# MCU_3_6.net
KiCad netlist of a schematic drawn in Altium Designer
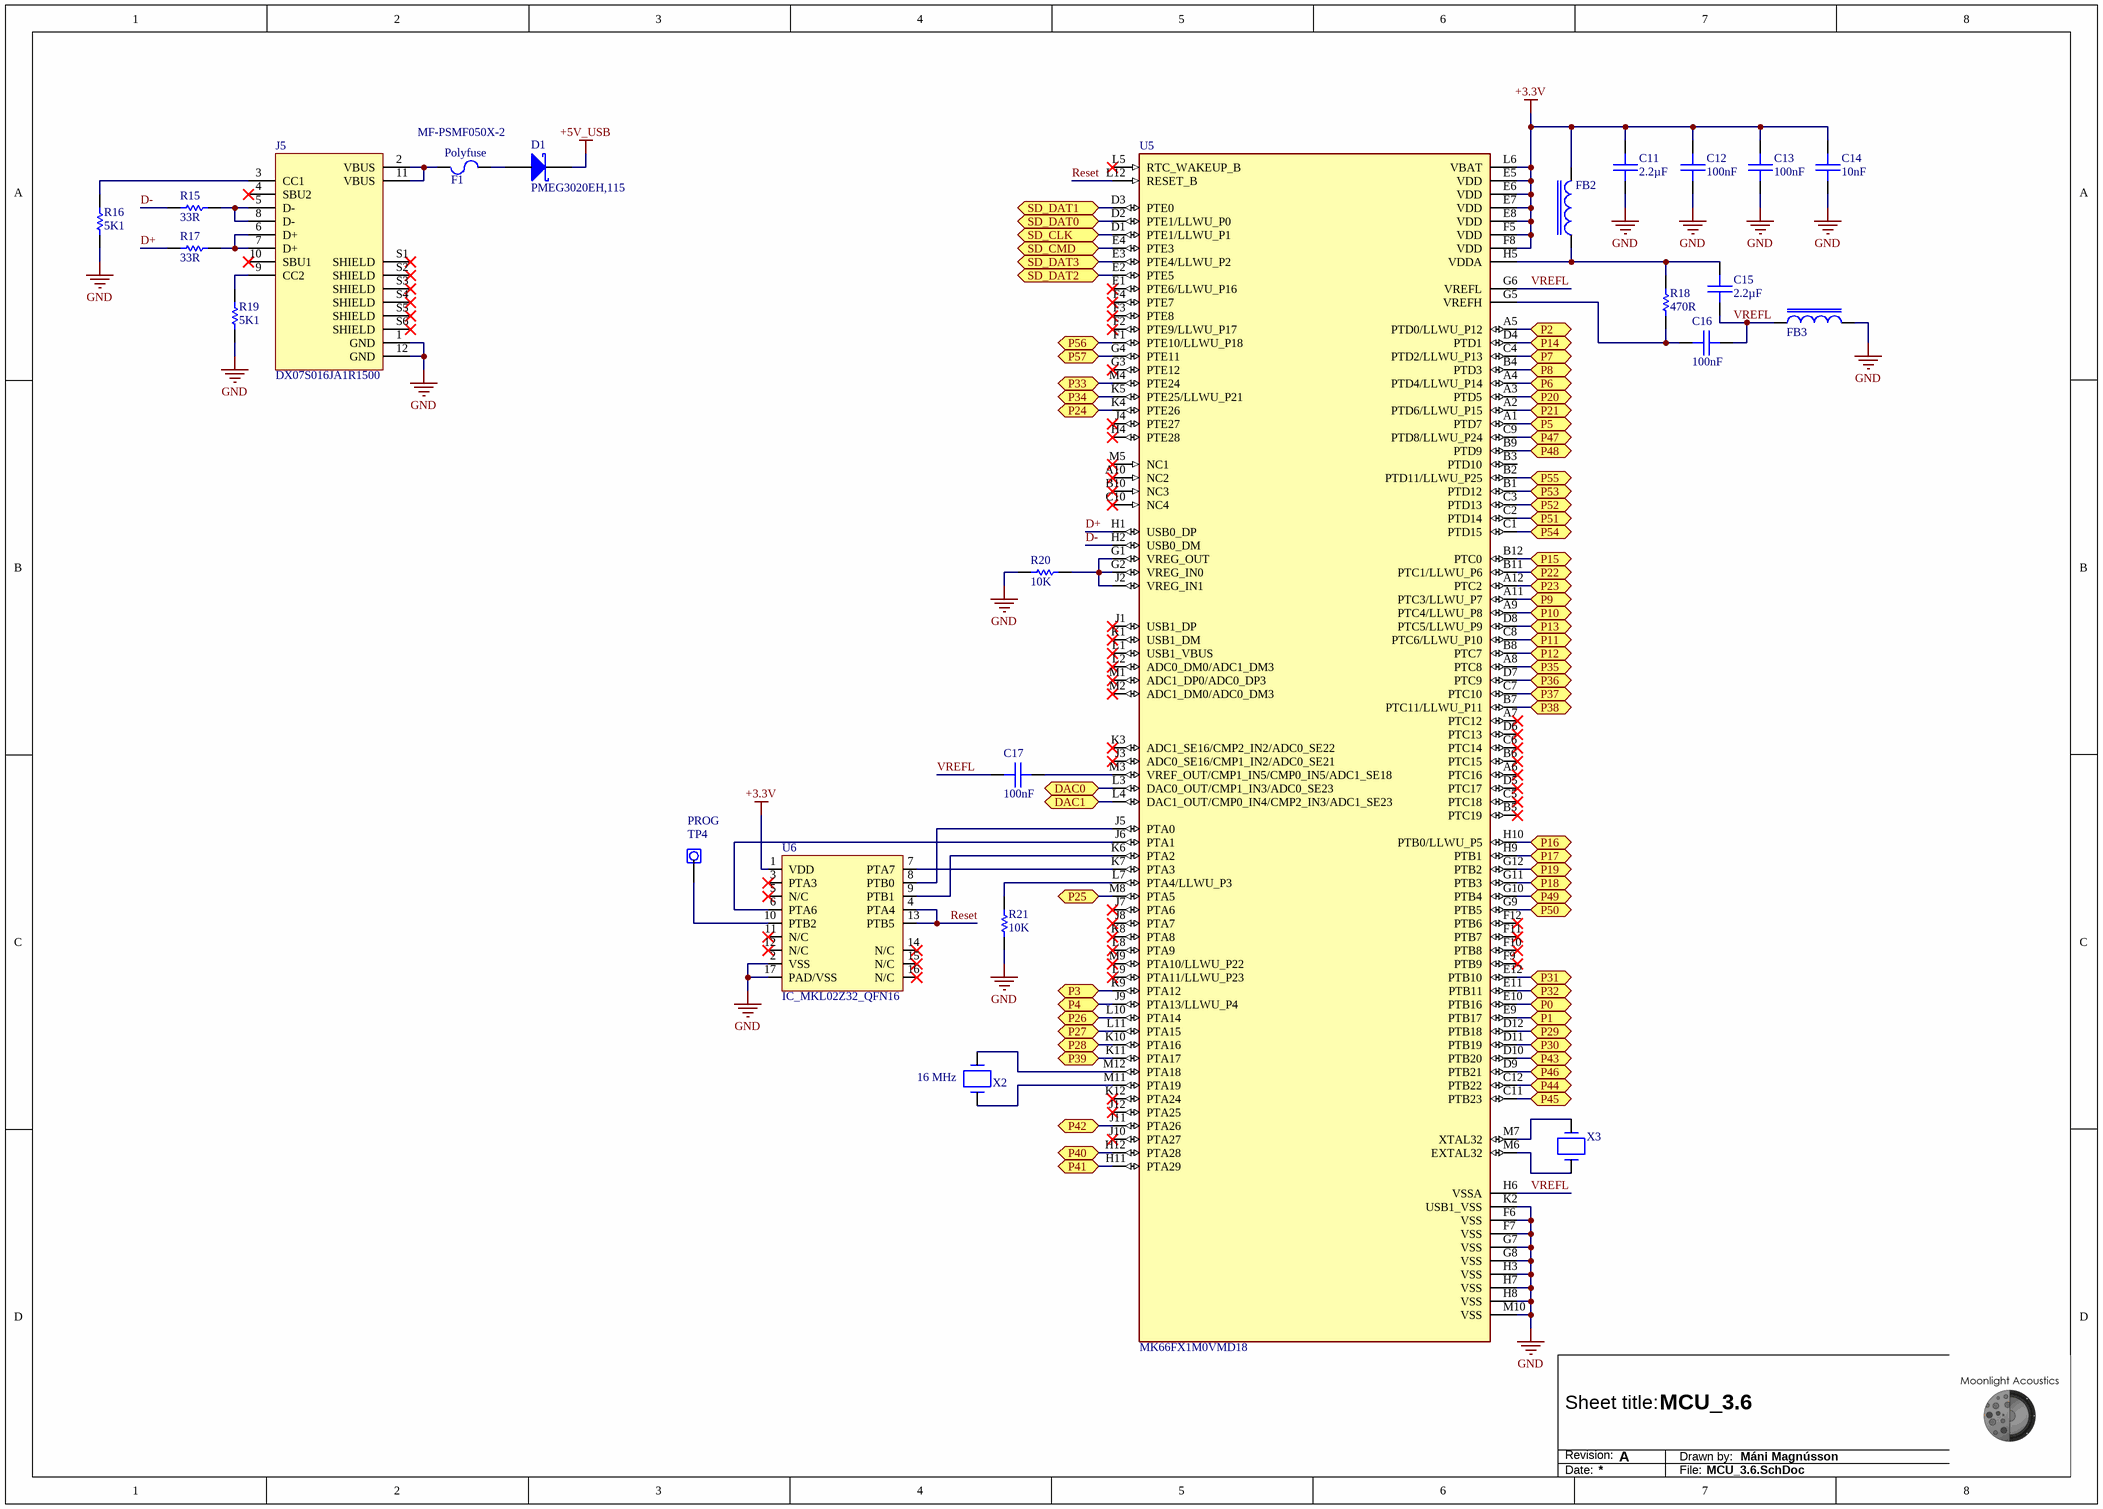
[diagram p0: MCU_3.6.SchDoc]

(export (version "E")
  (design (tool "Eeschema 10.0.6"))
  (components
    (comp (ref "C11")
      (value "2.2µF")
      (footprint "0603_CAP")
      (libsource (lib "Moonlight_Components") (part "Capacitor"))
    )
    (comp (ref "C12")
      (value "100nF")
      (footprint "0603_CAP")
      (libsource (lib "Moonlight_Components") (part "Capacitor"))
    )
    (comp (ref "C13")
      (value "100nF")
      (footprint "0603_CAP")
      (libsource (lib "Moonlight_Components") (part "Capacitor"))
    )
    (comp (ref "C14")
      (value "10nF")
      (footprint "0603_CAP")
      (libsource (lib "Moonlight_Components") (part "Capacitor"))
    )
    (comp (ref "C15")
      (value "2.2µF")
      (footprint "0603_CAP")
      (libsource (lib "Moonlight_Components") (part "Capacitor"))
    )
    (comp (ref "C16")
      (value "100nF")
      (footprint "0603_CAP")
      (libsource (lib "Moonlight_Components") (part "Capacitor"))
    )
    (comp (ref "C17")
      (value "100nF")
      (footprint "0603_CAP")
      (libsource (lib "Moonlight_Components") (part "Capacitor"))
    )
    (comp (ref "D1")
      (value "PMEG3020EH,115")
      (footprint "SOD-123")
      (libsource (lib "Moonlight_Components") (part "Schottky diode"))
    )
    (comp (ref "F1")
      (value "Polyfuse")
      (footprint "0805")
      (libsource (lib "Moonlight_Components") (part "Fuse"))
    )
    (comp (ref "FB2")
      (value "FBTH1608HL221-T")
      (footprint "0603_FERRITE")
      (description "Digikey part no.\r\n587-FBTH1608HL221-TCT-ND")
      (libsource (lib "") (part "Ferrite Bead_1"))
    )
    (comp (ref "FB3")
      (value "FBTH1608HL221-T")
      (footprint "0603_FERRITE")
      (description "Digikey part no.\r\n587-FBTH1608HL221-TCT-ND")
      (libsource (lib "Moonlight_Components") (part "Ferrite Bead"))
    )
    (comp (ref "J5")
      (value "DX07S016JA1R1500")
      (footprint "JAE_DX07S016JA1R1500")
      (description "USB 2.0 Type C Receptacle Dip Type, PCB Top Mount (Digikey part no. 670-DX07S016JA1R1500CT-ND)")
      (fields (field (name "MF") "JAE Electronics"))
      (libsource (lib "Moonlight_Components") (part "DX07S016JA1R1500"))
    )
    (comp (ref "R15")
      (value "33R")
      (footprint "0603_RES")
      (libsource (lib "Moonlight_Components") (part "Resistor"))
    )
    (comp (ref "R16")
      (value "5K1")
      (footprint "0603_RES")
      (libsource (lib "Moonlight_Components") (part "Resistor"))
    )
    (comp (ref "R17")
      (value "33R")
      (footprint "0603_RES")
      (libsource (lib "Moonlight_Components") (part "Resistor"))
    )
    (comp (ref "R18")
      (value "470R")
      (footprint "0603_RES")
      (libsource (lib "Moonlight_Components") (part "Resistor"))
    )
    (comp (ref "R19")
      (value "5K1")
      (footprint "0603_RES")
      (libsource (lib "Moonlight_Components") (part "Resistor"))
    )
    (comp (ref "R20")
      (value "10K")
      (footprint "0603_RES")
      (libsource (lib "Moonlight_Components") (part "Resistor"))
    )
    (comp (ref "R21")
      (value "10K")
      (footprint "0603_RES")
      (libsource (lib "Moonlight_Components") (part "Resistor"))
    )
    (comp (ref "TP4")
      (value "PROG")
      (footprint "Testpoint2")
      (libsource (lib "Moonlight_Components") (part "Testpoint"))
    )
    (comp (ref "U5")
      (value "MK66FX1M0VMD18")
      (footprint "BGA144C100P12X12_1300X1300X170")
      (description "32-bit ARM Cortex-M4F Microcontroller 180 MHz 144-MAPBGA\r\nDigiKey part no. 568-13335-ND")
      (fields (field (name "MF") "NXP USA"))
      (libsource (lib "Moonlight_Components") (part "MK66FX1M0VMD18"))
    )
    (comp (ref "U6")
      (value "IC_MKL02Z32_QFN16")
      (footprint "QFN50P300X300X65-17N")
      (description "Teensy bootloader")
      (fields (field (name "MP") "MKL02Z32VFG4") (field (name "MF") "NXP USA"))
      (libsource (lib "Moonlight_Components") (part "IC_MKL02Z32_QFN16"))
    )
    (comp (ref "X2")
      (value "NX3225SA-16.000000MHZ-B3")
      (footprint "XTAL_NX3225SA")
      (description "Digikey part no. 644-1099-1-ND")
      (libsource (lib "Moonlight_Components") (part "XTAL_16 MHz"))
    )
    (comp (ref "X3")
      (value "ABS07-166-32.768KHZ-T")
      (footprint "XTAL_ABS07-166")
      (description "Digikey part no. 535-14514-1-ND\r\nRequires 12pF load capacitors")
      (libsource (lib "Moonlight_Components") (part "XTAL_32.768 kHz"))
    )
  )
  (nets
    (net (code "1") (name "+3.3V") (class "Default")
      (node (ref "C11") (pin "1") (pinfunction "1_1") (pintype "passive"))
      (node (ref "C12") (pin "1") (pinfunction "1_1") (pintype "passive"))
      (node (ref "C13") (pin "1") (pinfunction "1_1") (pintype "passive"))
      (node (ref "C14") (pin "1") (pinfunction "1_1") (pintype "passive"))
      (node (ref "FB2") (pin "2") (pinfunction "2_2") (pintype "passive"))
      (node (ref "U5") (pin "E5") (pinfunction "VDD_E5") (pintype "power_in"))
      (node (ref "U5") (pin "E6") (pinfunction "VDD_E6") (pintype "power_in"))
      (node (ref "U5") (pin "E7") (pinfunction "VDD_E7") (pintype "power_in"))
      (node (ref "U5") (pin "E8") (pinfunction "VDD_E8") (pintype "power_in"))
      (node (ref "U5") (pin "F5") (pinfunction "VDD_F5") (pintype "power_in"))
      (node (ref "U5") (pin "F8") (pinfunction "VDD_F8") (pintype "power_in"))
      (node (ref "U5") (pin "L6") (pinfunction "VBAT_L6") (pintype "power_in"))
      (node (ref "U6") (pin "1") (pinfunction "VDD_1") (pintype "power_in"))
    )
    (net (code "2") (name "+5V_USB") (class "Default")
      (node (ref "D1") (pin "2") (pinfunction "K_2") (pintype "passive"))
    )
    (net (code "3") (name "/D+") (class "Default")
      (node (ref "R17") (pin "1") (pinfunction "1_1") (pintype "passive"))
      (node (ref "U5") (pin "H1") (pinfunction "USB0_DP_H1") (pintype "bidirectional"))
    )
    (net (code "4") (name "/D-") (class "Default")
      (node (ref "R15") (pin "1") (pinfunction "1_1") (pintype "passive"))
      (node (ref "U5") (pin "H2") (pinfunction "USB0_DM_H2") (pintype "bidirectional"))
    )
    (net (code "5") (name "/DAC0") (class "Default")
      (node (ref "U5") (pin "L3") (pinfunction "DAC0_OUT/CMP1_IN3/ADC0_SE23_L3") (pintype "bidirectional"))
    )
    (net (code "6") (name "/DAC1") (class "Default")
      (node (ref "U5") (pin "L4") (pinfunction "DAC1_OUT/CMP0_IN4/CMP2_IN3/ADC1_SE23_L4") (pintype "bidirectional"))
    )
    (net (code "7") (name "/P0") (class "Default")
      (node (ref "U5") (pin "E10") (pinfunction "PTB16_E10") (pintype "bidirectional"))
    )
    (net (code "8") (name "/P1") (class "Default")
      (node (ref "U5") (pin "E9") (pinfunction "PTB17_E9") (pintype "bidirectional"))
    )
    (net (code "9") (name "/P2") (class "Default")
      (node (ref "U5") (pin "A5") (pinfunction "PTD0/LLWU_P12_A5") (pintype "bidirectional"))
    )
    (net (code "10") (name "/P3") (class "Default")
      (node (ref "U5") (pin "K9") (pinfunction "PTA12_K9") (pintype "bidirectional"))
    )
    (net (code "11") (name "/P4") (class "Default")
      (node (ref "U5") (pin "J9") (pinfunction "PTA13/LLWU_P4_J9") (pintype "bidirectional"))
    )
    (net (code "12") (name "/P5") (class "Default")
      (node (ref "U5") (pin "A1") (pinfunction "PTD7_A1") (pintype "bidirectional"))
    )
    (net (code "13") (name "/P6") (class "Default")
      (node (ref "U5") (pin "A4") (pinfunction "PTD4/LLWU_P14_A4") (pintype "bidirectional"))
    )
    (net (code "14") (name "/P7") (class "Default")
      (node (ref "U5") (pin "C4") (pinfunction "PTD2/LLWU_P13_C4") (pintype "bidirectional"))
    )
    (net (code "15") (name "/P8") (class "Default")
      (node (ref "U5") (pin "B4") (pinfunction "PTD3_B4") (pintype "bidirectional"))
    )
    (net (code "16") (name "/P9") (class "Default")
      (node (ref "U5") (pin "A11") (pinfunction "PTC3/LLWU_P7_A11") (pintype "bidirectional"))
    )
    (net (code "17") (name "/P10") (class "Default")
      (node (ref "U5") (pin "A9") (pinfunction "PTC4/LLWU_P8_A9") (pintype "bidirectional"))
    )
    (net (code "18") (name "/P11") (class "Default")
      (node (ref "U5") (pin "C8") (pinfunction "PTC6/LLWU_P10_C8") (pintype "bidirectional"))
    )
    (net (code "19") (name "/P12") (class "Default")
      (node (ref "U5") (pin "B8") (pinfunction "PTC7_B8") (pintype "bidirectional"))
    )
    (net (code "20") (name "/P13") (class "Default")
      (node (ref "U5") (pin "D8") (pinfunction "PTC5/LLWU_P9_D8") (pintype "bidirectional"))
    )
    (net (code "21") (name "/P14") (class "Default")
      (node (ref "U5") (pin "D4") (pinfunction "PTD1_D4") (pintype "bidirectional"))
    )
    (net (code "22") (name "/P15") (class "Default")
      (node (ref "U5") (pin "B12") (pinfunction "PTC0_B12") (pintype "bidirectional"))
    )
    (net (code "23") (name "/P16") (class "Default")
      (node (ref "U5") (pin "H10") (pinfunction "PTB0/LLWU_P5_H10") (pintype "bidirectional"))
    )
    (net (code "24") (name "/P17") (class "Default")
      (node (ref "U5") (pin "H9") (pinfunction "PTB1_H9") (pintype "bidirectional"))
    )
    (net (code "25") (name "/P18") (class "Default")
      (node (ref "U5") (pin "G11") (pinfunction "PTB3_G11") (pintype "bidirectional"))
    )
    (net (code "26") (name "/P19") (class "Default")
      (node (ref "U5") (pin "G12") (pinfunction "PTB2_G12") (pintype "bidirectional"))
    )
    (net (code "27") (name "/P20") (class "Default")
      (node (ref "U5") (pin "A3") (pinfunction "PTD5_A3") (pintype "bidirectional"))
    )
    (net (code "28") (name "/P21") (class "Default")
      (node (ref "U5") (pin "A2") (pinfunction "PTD6/LLWU_P15_A2") (pintype "bidirectional"))
    )
    (net (code "29") (name "/P22") (class "Default")
      (node (ref "U5") (pin "B11") (pinfunction "PTC1/LLWU_P6_B11") (pintype "bidirectional"))
    )
    (net (code "30") (name "/P23") (class "Default")
      (node (ref "U5") (pin "A12") (pinfunction "PTC2_A12") (pintype "bidirectional"))
    )
    (net (code "31") (name "/P24") (class "Default")
      (node (ref "U5") (pin "K4") (pinfunction "PTE26_K4") (pintype "bidirectional"))
    )
    (net (code "32") (name "/P25") (class "Default")
      (node (ref "U5") (pin "M8") (pinfunction "PTA5_M8") (pintype "bidirectional"))
    )
    (net (code "33") (name "/P26") (class "Default")
      (node (ref "U5") (pin "L10") (pinfunction "PTA14_L10") (pintype "bidirectional"))
    )
    (net (code "34") (name "/P27") (class "Default")
      (node (ref "U5") (pin "L11") (pinfunction "PTA15_L11") (pintype "bidirectional"))
    )
    (net (code "35") (name "/P28") (class "Default")
      (node (ref "U5") (pin "K10") (pinfunction "PTA16_K10") (pintype "bidirectional"))
    )
    (net (code "36") (name "/P29") (class "Default")
      (node (ref "U5") (pin "D12") (pinfunction "PTB18_D12") (pintype "bidirectional"))
    )
    (net (code "37") (name "/P30") (class "Default")
      (node (ref "U5") (pin "D11") (pinfunction "PTB19_D11") (pintype "bidirectional"))
    )
    (net (code "38") (name "/P31") (class "Default")
      (node (ref "U5") (pin "E12") (pinfunction "PTB10_E12") (pintype "bidirectional"))
    )
    (net (code "39") (name "/P32") (class "Default")
      (node (ref "U5") (pin "E11") (pinfunction "PTB11_E11") (pintype "bidirectional"))
    )
    (net (code "40") (name "/P33") (class "Default")
      (node (ref "U5") (pin "M4") (pinfunction "PTE24_M4") (pintype "bidirectional"))
    )
    (net (code "41") (name "/P34") (class "Default")
      (node (ref "U5") (pin "K5") (pinfunction "PTE25/LLWU_P21_K5") (pintype "bidirectional"))
    )
    (net (code "42") (name "/P35") (class "Default")
      (node (ref "U5") (pin "A8") (pinfunction "PTC8_A8") (pintype "bidirectional"))
    )
    (net (code "43") (name "/P36") (class "Default")
      (node (ref "U5") (pin "D7") (pinfunction "PTC9_D7") (pintype "bidirectional"))
    )
    (net (code "44") (name "/P37") (class "Default")
      (node (ref "U5") (pin "C7") (pinfunction "PTC10_C7") (pintype "bidirectional"))
    )
    (net (code "45") (name "/P38") (class "Default")
      (node (ref "U5") (pin "B7") (pinfunction "PTC11/LLWU_P11_B7") (pintype "bidirectional"))
    )
    (net (code "46") (name "/P39") (class "Default")
      (node (ref "U5") (pin "K11") (pinfunction "PTA17_K11") (pintype "bidirectional"))
    )
    (net (code "47") (name "/P40") (class "Default")
      (node (ref "U5") (pin "H12") (pinfunction "PTA28_H12") (pintype "bidirectional"))
    )
    (net (code "48") (name "/P41") (class "Default")
      (node (ref "U5") (pin "H11") (pinfunction "PTA29_H11") (pintype "bidirectional"))
    )
    (net (code "49") (name "/P42") (class "Default")
      (node (ref "U5") (pin "J11") (pinfunction "PTA26_J11") (pintype "bidirectional"))
    )
    (net (code "50") (name "/P43") (class "Default")
      (node (ref "U5") (pin "D10") (pinfunction "PTB20_D10") (pintype "bidirectional"))
    )
    (net (code "51") (name "/P44") (class "Default")
      (node (ref "U5") (pin "C12") (pinfunction "PTB22_C12") (pintype "bidirectional"))
    )
    (net (code "52") (name "/P45") (class "Default")
      (node (ref "U5") (pin "C11") (pinfunction "PTB23_C11") (pintype "bidirectional"))
    )
    (net (code "53") (name "/P46") (class "Default")
      (node (ref "U5") (pin "D9") (pinfunction "PTB21_D9") (pintype "bidirectional"))
    )
    (net (code "54") (name "/P47") (class "Default")
      (node (ref "U5") (pin "C9") (pinfunction "PTD8/LLWU_P24_C9") (pintype "bidirectional"))
    )
    (net (code "55") (name "/P48") (class "Default")
      (node (ref "U5") (pin "B9") (pinfunction "PTD9_B9") (pintype "bidirectional"))
    )
    (net (code "56") (name "/P49") (class "Default")
      (node (ref "U5") (pin "G10") (pinfunction "PTB4_G10") (pintype "bidirectional"))
    )
    (net (code "57") (name "/P50") (class "Default")
      (node (ref "U5") (pin "G9") (pinfunction "PTB5_G9") (pintype "bidirectional"))
    )
    (net (code "58") (name "/P51") (class "Default")
      (node (ref "U5") (pin "C2") (pinfunction "PTD14_C2") (pintype "bidirectional"))
    )
    (net (code "59") (name "/P52") (class "Default")
      (node (ref "U5") (pin "C3") (pinfunction "PTD13_C3") (pintype "bidirectional"))
    )
    (net (code "60") (name "/P53") (class "Default")
      (node (ref "U5") (pin "B1") (pinfunction "PTD12_B1") (pintype "bidirectional"))
    )
    (net (code "61") (name "/P54") (class "Default")
      (node (ref "U5") (pin "C1") (pinfunction "PTD15_C1") (pintype "bidirectional"))
    )
    (net (code "62") (name "/P55") (class "Default")
      (node (ref "U5") (pin "B2") (pinfunction "PTD11/LLWU_P25_B2") (pintype "bidirectional"))
    )
    (net (code "63") (name "/P56") (class "Default")
      (node (ref "U5") (pin "F1") (pinfunction "PTE10/LLWU_P18_F1") (pintype "bidirectional"))
    )
    (net (code "64") (name "/P57") (class "Default")
      (node (ref "U5") (pin "G4") (pinfunction "PTE11_G4") (pintype "bidirectional"))
    )
    (net (code "65") (name "/Reset") (class "Default")
      (node (ref "U5") (pin "L12") (pinfunction "RESET_B_L12") (pintype "input"))
      (node (ref "U6") (pin "13") (pinfunction "PTB5_13") (pintype "bidirectional"))
      (node (ref "U6") (pin "4") (pinfunction "PTA4_4") (pintype "bidirectional"))
    )
    (net (code "66") (name "/SD_CLK") (class "Default")
      (node (ref "U5") (pin "D1") (pinfunction "PTE1/LLWU_P1_D1") (pintype "bidirectional"))
    )
    (net (code "67") (name "/SD_CMD") (class "Default")
      (node (ref "U5") (pin "E4") (pinfunction "PTE3_E4") (pintype "bidirectional"))
    )
    (net (code "68") (name "/SD_DAT0") (class "Default")
      (node (ref "U5") (pin "D2") (pinfunction "PTE1/LLWU_P0_D2") (pintype "bidirectional"))
    )
    (net (code "69") (name "/SD_DAT1") (class "Default")
      (node (ref "U5") (pin "D3") (pinfunction "PTE0_D3") (pintype "bidirectional"))
    )
    (net (code "70") (name "/SD_DAT2") (class "Default")
      (node (ref "U5") (pin "E2") (pinfunction "PTE5_E2") (pintype "bidirectional"))
    )
    (net (code "71") (name "/SD_DAT3") (class "Default")
      (node (ref "U5") (pin "E3") (pinfunction "PTE4/LLWU_P2_E3") (pintype "bidirectional"))
    )
    (net (code "72") (name "/VREFL") (class "Default")
      (node (ref "C15") (pin "2") (pinfunction "2_2") (pintype "passive"))
      (node (ref "C16") (pin "2") (pinfunction "2_2") (pintype "passive"))
      (node (ref "C17") (pin "1") (pinfunction "1_1") (pintype "passive"))
      (node (ref "FB3") (pin "2") (pinfunction "2_2") (pintype "passive"))
      (node (ref "U5") (pin "G6") (pinfunction "VREFL_G6") (pintype "power_in"))
      (node (ref "U5") (pin "H6") (pinfunction "VSSA_H6") (pintype "power_in"))
    )
    (net (code "73") (name "GND") (class "Default")
      (node (ref "C11") (pin "2") (pinfunction "2_2") (pintype "passive"))
      (node (ref "C12") (pin "2") (pinfunction "2_2") (pintype "passive"))
      (node (ref "C13") (pin "2") (pinfunction "2_2") (pintype "passive"))
      (node (ref "C14") (pin "2") (pinfunction "2_2") (pintype "passive"))
      (node (ref "FB3") (pin "1") (pinfunction "1_1") (pintype "passive"))
      (node (ref "J5") (pin "1") (pinfunction "GND_1") (pintype "power_in"))
      (node (ref "J5") (pin "12") (pinfunction "GND_12") (pintype "power_in"))
      (node (ref "R16") (pin "2") (pinfunction "2_2") (pintype "passive"))
      (node (ref "R19") (pin "2") (pinfunction "2_2") (pintype "passive"))
      (node (ref "R20") (pin "1") (pinfunction "1_1") (pintype "passive"))
      (node (ref "R21") (pin "1") (pinfunction "1_1") (pintype "passive"))
      (node (ref "U5") (pin "F6") (pinfunction "VSS_F6") (pintype "power_in"))
      (node (ref "U5") (pin "F7") (pinfunction "VSS_F7") (pintype "power_in"))
      (node (ref "U5") (pin "G7") (pinfunction "VSS_G7") (pintype "power_in"))
      (node (ref "U5") (pin "G8") (pinfunction "VSS_G8") (pintype "power_in"))
      (node (ref "U5") (pin "H3") (pinfunction "VSS_H3") (pintype "power_in"))
      (node (ref "U5") (pin "H7") (pinfunction "VSS_H7") (pintype "power_in"))
      (node (ref "U5") (pin "H8") (pinfunction "VSS_H8") (pintype "power_in"))
      (node (ref "U5") (pin "K2") (pinfunction "USB1_VSS_K2") (pintype "power_in"))
      (node (ref "U5") (pin "M10") (pinfunction "VSS_M10") (pintype "power_in"))
      (node (ref "U6") (pin "17") (pinfunction "PAD/VSS_17") (pintype "power_in"))
      (node (ref "U6") (pin "2") (pinfunction "VSS_2") (pintype "power_in"))
    )
    (net (code "74") (name "Net-(D1-A)") (class "Default")
      (node (ref "D1") (pin "1") (pinfunction "A_1") (pintype "passive"))
      (node (ref "F1") (pin "2") (pinfunction "2_2") (pintype "passive"))
    )
    (net (code "75") (name "Net-(F1-Pad1)") (class "Default")
      (node (ref "F1") (pin "1") (pinfunction "1_1") (pintype "passive"))
      (node (ref "J5") (pin "11") (pinfunction "VBUS_11") (pintype "power_in"))
      (node (ref "J5") (pin "2") (pinfunction "VBUS_2") (pintype "power_in"))
    )
    (net (code "76") (name "Net-(J5-CC1)") (class "Default")
      (node (ref "J5") (pin "3") (pinfunction "CC1_3") (pintype "passive"))
      (node (ref "R16") (pin "1") (pinfunction "1_1") (pintype "passive"))
    )
    (net (code "77") (name "Net-(J5-CC2)") (class "Default")
      (node (ref "J5") (pin "9") (pinfunction "CC2_9") (pintype "passive"))
      (node (ref "R19") (pin "1") (pinfunction "1_1") (pintype "passive"))
    )
    (net (code "78") (name "Net-(J5-D+-Pad6)") (class "Default")
      (node (ref "J5") (pin "6") (pinfunction "D+_6") (pintype "passive"))
      (node (ref "J5") (pin "7") (pinfunction "D+_7") (pintype "passive"))
      (node (ref "R17") (pin "2") (pinfunction "2_2") (pintype "passive"))
    )
    (net (code "79") (name "Net-(J5-D--Pad5)") (class "Default")
      (node (ref "J5") (pin "5") (pinfunction "D-_5") (pintype "passive"))
      (node (ref "J5") (pin "8") (pinfunction "D-_8") (pintype "passive"))
      (node (ref "R15") (pin "2") (pinfunction "2_2") (pintype "passive"))
    )
    (net (code "80") (name "Net-(U5-EXTAL32)") (class "Default")
      (node (ref "U5") (pin "M6") (pinfunction "EXTAL32_M6") (pintype "bidirectional"))
      (node (ref "X3") (pin "1") (pinfunction "1_1") (pintype "passive"))
    )
    (net (code "81") (name "Net-(U5-PTA0)") (class "Default")
      (node (ref "U5") (pin "J5") (pinfunction "PTA0_J5") (pintype "bidirectional"))
      (node (ref "U6") (pin "8") (pinfunction "PTB0_8") (pintype "bidirectional"))
    )
    (net (code "82") (name "Net-(U5-PTA1)") (class "Default")
      (node (ref "U5") (pin "J6") (pinfunction "PTA1_J6") (pintype "bidirectional"))
      (node (ref "U6") (pin "6") (pinfunction "PTA6_6") (pintype "bidirectional"))
    )
    (net (code "83") (name "Net-(U5-PTA2)") (class "Default")
      (node (ref "U5") (pin "K6") (pinfunction "PTA2_K6") (pintype "bidirectional"))
      (node (ref "U6") (pin "9") (pinfunction "PTB1_9") (pintype "bidirectional"))
    )
    (net (code "84") (name "Net-(U5-PTA3)") (class "Default")
      (node (ref "U5") (pin "K7") (pinfunction "PTA3_K7") (pintype "bidirectional"))
      (node (ref "U6") (pin "7") (pinfunction "PTA7_7") (pintype "bidirectional"))
    )
    (net (code "85") (name "Net-(U5-PTA4{slash}LLWU_P3)") (class "Default")
      (node (ref "R21") (pin "2") (pinfunction "2_2") (pintype "passive"))
      (node (ref "U5") (pin "L7") (pinfunction "PTA4/LLWU_P3_L7") (pintype "bidirectional"))
    )
    (net (code "86") (name "Net-(U5-PTA18)") (class "Default")
      (node (ref "U5") (pin "M12") (pinfunction "PTA18_M12") (pintype "bidirectional"))
      (node (ref "X2") (pin "3") (pinfunction "3_3") (pintype "passive"))
    )
    (net (code "87") (name "Net-(U5-PTA19)") (class "Default")
      (node (ref "U5") (pin "M11") (pinfunction "PTA19_M11") (pintype "bidirectional"))
      (node (ref "X2") (pin "1") (pinfunction "1_1") (pintype "passive"))
    )
    (net (code "88") (name "Net-(U5-VDDA)") (class "Default")
      (node (ref "C15") (pin "1") (pinfunction "1_1") (pintype "passive"))
      (node (ref "FB2") (pin "1") (pinfunction "1_1") (pintype "passive"))
      (node (ref "R18") (pin "1") (pinfunction "1_1") (pintype "passive"))
      (node (ref "U5") (pin "H5") (pinfunction "VDDA_H5") (pintype "power_in"))
    )
    (net (code "89") (name "Net-(U5-VREFH)") (class "Default")
      (node (ref "C16") (pin "1") (pinfunction "1_1") (pintype "passive"))
      (node (ref "R18") (pin "2") (pinfunction "2_2") (pintype "passive"))
      (node (ref "U5") (pin "G5") (pinfunction "VREFH_G5") (pintype "power_in"))
    )
    (net (code "90") (name "Net-(U5-VREF_OUT{slash}CMP1_IN5{slash}CMP0_IN5{slash}ADC1_SE18)") (class "Default")
      (node (ref "C17") (pin "2") (pinfunction "2_2") (pintype "passive"))
      (node (ref "U5") (pin "M3") (pinfunction "VREF_OUT/CMP1_IN5/CMP0_IN5/ADC1_SE18_M3") (pintype "bidirectional"))
    )
    (net (code "91") (name "Net-(U5-VREG_IN0)") (class "Default")
      (node (ref "R20") (pin "2") (pinfunction "2_2") (pintype "passive"))
      (node (ref "U5") (pin "G1") (pinfunction "VREG_OUT_G1") (pintype "bidirectional"))
      (node (ref "U5") (pin "G2") (pinfunction "VREG_IN0_G2") (pintype "bidirectional"))
      (node (ref "U5") (pin "J2") (pinfunction "VREG_IN1_J2") (pintype "bidirectional"))
    )
    (net (code "92") (name "Net-(U5-XTAL32)") (class "Default")
      (node (ref "U5") (pin "M7") (pinfunction "XTAL32_M7") (pintype "bidirectional"))
      (node (ref "X3") (pin "2") (pinfunction "2_2") (pintype "passive"))
    )
    (net (code "93") (name "Net-(U6-PTB2)") (class "Default")
      (node (ref "TP4") (pin "1") (pinfunction "1_1") (pintype "passive"))
      (node (ref "U6") (pin "10") (pinfunction "PTB2_10") (pintype "bidirectional"))
    )
    (net (code "94") (name "unconnected-(J5-SBU1-Pad10)") (class "Default")
      (node (ref "J5") (pin "10") (pinfunction "SBU1_10") (pintype "passive+no_connect"))
    )
    (net (code "95") (name "unconnected-(J5-SBU2-Pad4)") (class "Default")
      (node (ref "J5") (pin "4") (pinfunction "SBU2_4") (pintype "passive+no_connect"))
    )
    (net (code "96") (name "unconnected-(J5-SHIELD-PadS1)") (class "Default")
      (node (ref "J5") (pin "S1") (pinfunction "SHIELD_S1") (pintype "passive+no_connect"))
    )
    (net (code "97") (name "unconnected-(J5-SHIELD-PadS2)") (class "Default")
      (node (ref "J5") (pin "S2") (pinfunction "SHIELD_S2") (pintype "passive+no_connect"))
    )
    (net (code "98") (name "unconnected-(J5-SHIELD-PadS3)") (class "Default")
      (node (ref "J5") (pin "S3") (pinfunction "SHIELD_S3") (pintype "passive+no_connect"))
    )
    (net (code "99") (name "unconnected-(J5-SHIELD-PadS4)") (class "Default")
      (node (ref "J5") (pin "S4") (pinfunction "SHIELD_S4") (pintype "passive+no_connect"))
    )
    (net (code "100") (name "unconnected-(J5-SHIELD-PadS5)") (class "Default")
      (node (ref "J5") (pin "S5") (pinfunction "SHIELD_S5") (pintype "passive+no_connect"))
    )
    (net (code "101") (name "unconnected-(J5-SHIELD-PadS6)") (class "Default")
      (node (ref "J5") (pin "S6") (pinfunction "SHIELD_S6") (pintype "passive+no_connect"))
    )
    (net (code "102") (name "unconnected-(U5-ADC0_DM0{slash}ADC1_DM3-PadL2)") (class "Default")
      (node (ref "U5") (pin "L2") (pinfunction "ADC0_DM0/ADC1_DM3_L2") (pintype "bidirectional+no_connect"))
    )
    (net (code "103") (name "unconnected-(U5-ADC0_SE16{slash}CMP1_IN2{slash}ADC0_SE21-PadJ3)") (class "Default")
      (node (ref "U5") (pin "J3") (pinfunction "ADC0_SE16/CMP1_IN2/ADC0_SE21_J3") (pintype "bidirectional+no_connect"))
    )
    (net (code "104") (name "unconnected-(U5-ADC1_DM0{slash}ADC0_DM3-PadM2)") (class "Default")
      (node (ref "U5") (pin "M2") (pinfunction "ADC1_DM0/ADC0_DM3_M2") (pintype "bidirectional+no_connect"))
    )
    (net (code "105") (name "unconnected-(U5-ADC1_DP0{slash}ADC0_DP3-PadM1)") (class "Default")
      (node (ref "U5") (pin "M1") (pinfunction "ADC1_DP0/ADC0_DP3_M1") (pintype "bidirectional+no_connect"))
    )
    (net (code "106") (name "unconnected-(U5-ADC1_SE16{slash}CMP2_IN2{slash}ADC0_SE22-PadK3)") (class "Default")
      (node (ref "U5") (pin "K3") (pinfunction "ADC1_SE16/CMP2_IN2/ADC0_SE22_K3") (pintype "bidirectional+no_connect"))
    )
    (net (code "107") (name "unconnected-(U5-NC1-PadM5)") (class "Default")
      (node (ref "U5") (pin "M5") (pinfunction "NC1_M5") (pintype "input+no_connect"))
    )
    (net (code "108") (name "unconnected-(U5-NC2-PadA10)") (class "Default")
      (node (ref "U5") (pin "A10") (pinfunction "NC2_A10") (pintype "input+no_connect"))
    )
    (net (code "109") (name "unconnected-(U5-NC3-PadB10)") (class "Default")
      (node (ref "U5") (pin "B10") (pinfunction "NC3_B10") (pintype "input+no_connect"))
    )
    (net (code "110") (name "unconnected-(U5-NC4-PadC10)") (class "Default")
      (node (ref "U5") (pin "C10") (pinfunction "NC4_C10") (pintype "input+no_connect"))
    )
    (net (code "111") (name "unconnected-(U5-PTA6-PadJ7)") (class "Default")
      (node (ref "U5") (pin "J7") (pinfunction "PTA6_J7") (pintype "bidirectional+no_connect"))
    )
    (net (code "112") (name "unconnected-(U5-PTA7-PadJ8)") (class "Default")
      (node (ref "U5") (pin "J8") (pinfunction "PTA7_J8") (pintype "bidirectional+no_connect"))
    )
    (net (code "113") (name "unconnected-(U5-PTA8-PadK8)") (class "Default")
      (node (ref "U5") (pin "K8") (pinfunction "PTA8_K8") (pintype "bidirectional+no_connect"))
    )
    (net (code "114") (name "unconnected-(U5-PTA9-PadL8)") (class "Default")
      (node (ref "U5") (pin "L8") (pinfunction "PTA9_L8") (pintype "bidirectional+no_connect"))
    )
    (net (code "115") (name "unconnected-(U5-PTA10{slash}LLWU_P22-PadM9)") (class "Default")
      (node (ref "U5") (pin "M9") (pinfunction "PTA10/LLWU_P22_M9") (pintype "bidirectional+no_connect"))
    )
    (net (code "116") (name "unconnected-(U5-PTA11{slash}LLWU_P23-PadL9)") (class "Default")
      (node (ref "U5") (pin "L9") (pinfunction "PTA11/LLWU_P23_L9") (pintype "bidirectional+no_connect"))
    )
    (net (code "117") (name "unconnected-(U5-PTA24-PadK12)") (class "Default")
      (node (ref "U5") (pin "K12") (pinfunction "PTA24_K12") (pintype "bidirectional+no_connect"))
    )
    (net (code "118") (name "unconnected-(U5-PTA25-PadJ12)") (class "Default")
      (node (ref "U5") (pin "J12") (pinfunction "PTA25_J12") (pintype "bidirectional+no_connect"))
    )
    (net (code "119") (name "unconnected-(U5-PTA27-PadJ10)") (class "Default")
      (node (ref "U5") (pin "J10") (pinfunction "PTA27_J10") (pintype "bidirectional+no_connect"))
    )
    (net (code "120") (name "unconnected-(U5-PTB6-PadF12)") (class "Default")
      (node (ref "U5") (pin "F12") (pinfunction "PTB6_F12") (pintype "bidirectional+no_connect"))
    )
    (net (code "121") (name "unconnected-(U5-PTB7-PadF11)") (class "Default")
      (node (ref "U5") (pin "F11") (pinfunction "PTB7_F11") (pintype "bidirectional+no_connect"))
    )
    (net (code "122") (name "unconnected-(U5-PTB8-PadF10)") (class "Default")
      (node (ref "U5") (pin "F10") (pinfunction "PTB8_F10") (pintype "bidirectional+no_connect"))
    )
    (net (code "123") (name "unconnected-(U5-PTB9-PadF9)") (class "Default")
      (node (ref "U5") (pin "F9") (pinfunction "PTB9_F9") (pintype "bidirectional+no_connect"))
    )
    (net (code "124") (name "unconnected-(U5-PTC12-PadA7)") (class "Default")
      (node (ref "U5") (pin "A7") (pinfunction "PTC12_A7") (pintype "bidirectional+no_connect"))
    )
    (net (code "125") (name "unconnected-(U5-PTC13-PadD6)") (class "Default")
      (node (ref "U5") (pin "D6") (pinfunction "PTC13_D6") (pintype "bidirectional+no_connect"))
    )
    (net (code "126") (name "unconnected-(U5-PTC14-PadC6)") (class "Default")
      (node (ref "U5") (pin "C6") (pinfunction "PTC14_C6") (pintype "bidirectional+no_connect"))
    )
    (net (code "127") (name "unconnected-(U5-PTC15-PadB6)") (class "Default")
      (node (ref "U5") (pin "B6") (pinfunction "PTC15_B6") (pintype "bidirectional+no_connect"))
    )
    (net (code "128") (name "unconnected-(U5-PTC16-PadA6)") (class "Default")
      (node (ref "U5") (pin "A6") (pinfunction "PTC16_A6") (pintype "bidirectional+no_connect"))
    )
    (net (code "129") (name "unconnected-(U5-PTC17-PadD5)") (class "Default")
      (node (ref "U5") (pin "D5") (pinfunction "PTC17_D5") (pintype "bidirectional+no_connect"))
    )
    (net (code "130") (name "unconnected-(U5-PTC18-PadC5)") (class "Default")
      (node (ref "U5") (pin "C5") (pinfunction "PTC18_C5") (pintype "bidirectional+no_connect"))
    )
    (net (code "131") (name "unconnected-(U5-PTC19-PadB5)") (class "Default")
      (node (ref "U5") (pin "B5") (pinfunction "PTC19_B5") (pintype "bidirectional+no_connect"))
    )
    (net (code "132") (name "unconnected-(U5-PTD10-PadB3)") (class "Default")
      (node (ref "U5") (pin "B3") (pinfunction "PTD10_B3") (pintype "bidirectional"))
    )
    (net (code "133") (name "unconnected-(U5-PTE6{slash}LLWU_P16-PadE1)") (class "Default")
      (node (ref "U5") (pin "E1") (pinfunction "PTE6/LLWU_P16_E1") (pintype "bidirectional+no_connect"))
    )
    (net (code "134") (name "unconnected-(U5-PTE7-PadF4)") (class "Default")
      (node (ref "U5") (pin "F4") (pinfunction "PTE7_F4") (pintype "bidirectional+no_connect"))
    )
    (net (code "135") (name "unconnected-(U5-PTE8-PadF3)") (class "Default")
      (node (ref "U5") (pin "F3") (pinfunction "PTE8_F3") (pintype "bidirectional+no_connect"))
    )
    (net (code "136") (name "unconnected-(U5-PTE9{slash}LLWU_P17-PadF2)") (class "Default")
      (node (ref "U5") (pin "F2") (pinfunction "PTE9/LLWU_P17_F2") (pintype "bidirectional+no_connect"))
    )
    (net (code "137") (name "unconnected-(U5-PTE12-PadG3)") (class "Default")
      (node (ref "U5") (pin "G3") (pinfunction "PTE12_G3") (pintype "bidirectional+no_connect"))
    )
    (net (code "138") (name "unconnected-(U5-PTE27-PadJ4)") (class "Default")
      (node (ref "U5") (pin "J4") (pinfunction "PTE27_J4") (pintype "bidirectional+no_connect"))
    )
    (net (code "139") (name "unconnected-(U5-PTE28-PadH4)") (class "Default")
      (node (ref "U5") (pin "H4") (pinfunction "PTE28_H4") (pintype "bidirectional+no_connect"))
    )
    (net (code "140") (name "unconnected-(U5-RTC_WAKEUP_B-PadL5)") (class "Default")
      (node (ref "U5") (pin "L5") (pinfunction "RTC_WAKEUP_B_L5") (pintype "input+no_connect"))
    )
    (net (code "141") (name "unconnected-(U5-USB1_DM-PadK1)") (class "Default")
      (node (ref "U5") (pin "K1") (pinfunction "USB1_DM_K1") (pintype "bidirectional+no_connect"))
    )
    (net (code "142") (name "unconnected-(U5-USB1_DP-PadJ1)") (class "Default")
      (node (ref "U5") (pin "J1") (pinfunction "USB1_DP_J1") (pintype "bidirectional+no_connect"))
    )
    (net (code "143") (name "unconnected-(U5-USB1_VBUS-PadL1)") (class "Default")
      (node (ref "U5") (pin "L1") (pinfunction "USB1_VBUS_L1") (pintype "bidirectional+no_connect"))
    )
    (net (code "144") (name "unconnected-(U6-N{slash}C-Pad5)") (class "Default")
      (node (ref "U6") (pin "5") (pinfunction "N/C_5") (pintype "bidirectional+no_connect"))
    )
    (net (code "145") (name "unconnected-(U6-N{slash}C-Pad11)") (class "Default")
      (node (ref "U6") (pin "11") (pinfunction "N/C_11") (pintype "bidirectional+no_connect"))
    )
    (net (code "146") (name "unconnected-(U6-N{slash}C-Pad12)") (class "Default")
      (node (ref "U6") (pin "12") (pinfunction "N/C_12") (pintype "bidirectional+no_connect"))
    )
    (net (code "147") (name "unconnected-(U6-N{slash}C-Pad14)") (class "Default")
      (node (ref "U6") (pin "14") (pinfunction "N/C_14") (pintype "bidirectional+no_connect"))
    )
    (net (code "148") (name "unconnected-(U6-N{slash}C-Pad15)") (class "Default")
      (node (ref "U6") (pin "15") (pinfunction "N/C_15") (pintype "bidirectional+no_connect"))
    )
    (net (code "149") (name "unconnected-(U6-N{slash}C-Pad16)") (class "Default")
      (node (ref "U6") (pin "16") (pinfunction "N/C_16") (pintype "bidirectional+no_connect"))
    )
    (net (code "150") (name "unconnected-(U6-PTA3-Pad3)") (class "Default")
      (node (ref "U6") (pin "3") (pinfunction "PTA3_3") (pintype "bidirectional+no_connect"))
    )
  )
)
